# Shield_Semaforo.net
KiCad netlist of a schematic drawn in EAGLE
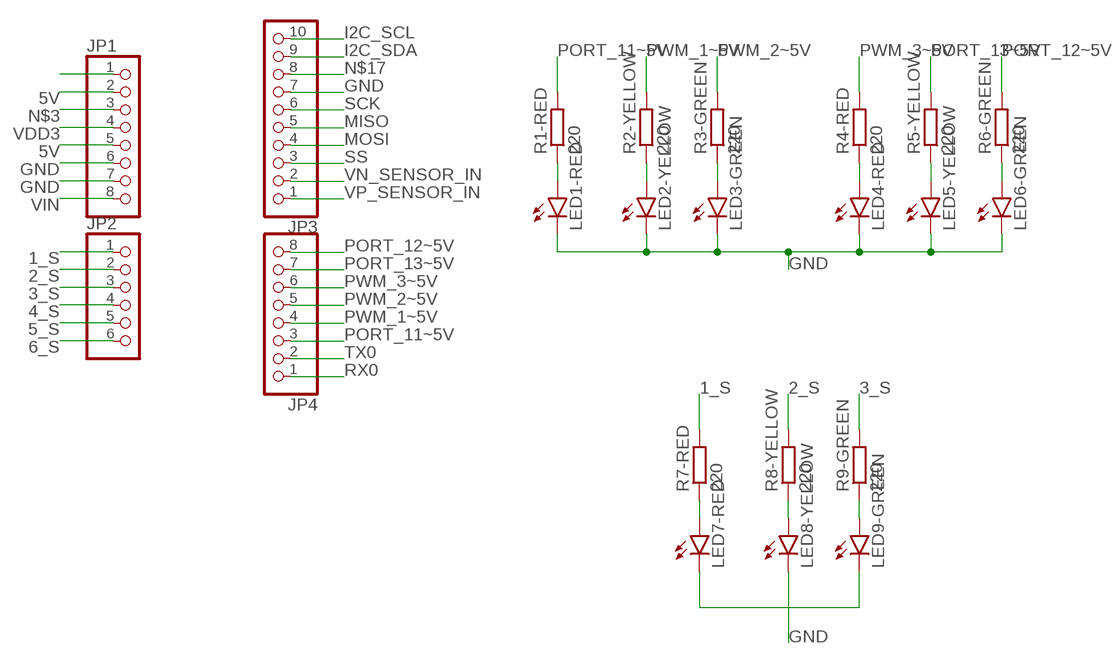
[diagram p0: schematic, sheet 1]

(export (version "E")
  (design (tool "Eeschema 10.0.6"))
  (components
    (comp (ref "JP1")
      (value "PINHD-1X8_2.54-SMD")
      (footprint "eagle-import:1X08SMD")
      (libsource (lib "eagle-import") (part "PINHD-1X8_2.54-SMD"))
    )
    (comp (ref "JP2")
      (value "PINHD-1X6_2.54-SMD")
      (footprint "eagle-import:1X06SMD")
      (libsource (lib "eagle-import") (part "PINHD-1X6_2.54-SMD"))
    )
    (comp (ref "JP3")
      (value "PINHD-1X10_2.54-SMD")
      (footprint "eagle-import:1X10SMD")
      (libsource (lib "eagle-import") (part "PINHD-1X10_2.54-SMD"))
    )
    (comp (ref "JP4")
      (value "PINHD-1X8_2.54-SMD")
      (footprint "eagle-import:1X08SMD")
      (libsource (lib "eagle-import") (part "PINHD-1X8_2.54-SMD"))
    )
    (comp (ref "LED1-RED")
      (value "LED5MM")
      (footprint "eagle-import:LED5MM")
      (libsource (lib "eagle-import") (part "LED5MM"))
    )
    (comp (ref "LED2-YELLOW")
      (value "LED5MM")
      (footprint "eagle-import:LED5MM")
      (libsource (lib "eagle-import") (part "LED5MM"))
    )
    (comp (ref "LED3-GREEN")
      (value "LED5MM")
      (footprint "eagle-import:LED5MM")
      (libsource (lib "eagle-import") (part "LED5MM"))
    )
    (comp (ref "LED4-RED")
      (value "LED5MM")
      (footprint "eagle-import:LED5MM")
      (libsource (lib "eagle-import") (part "LED5MM"))
    )
    (comp (ref "LED5-YELLOW")
      (value "LED5MM")
      (footprint "eagle-import:LED5MM")
      (libsource (lib "eagle-import") (part "LED5MM"))
    )
    (comp (ref "LED6-GREEN")
      (value "LED5MM")
      (footprint "eagle-import:LED5MM")
      (libsource (lib "eagle-import") (part "LED5MM"))
    )
    (comp (ref "LED7-RED")
      (value "LED5MM")
      (footprint "eagle-import:LED5MM")
      (libsource (lib "eagle-import") (part "LED5MM"))
    )
    (comp (ref "LED8-YELLOW")
      (value "LED5MM")
      (footprint "eagle-import:LED5MM")
      (libsource (lib "eagle-import") (part "LED5MM"))
    )
    (comp (ref "LED9-GREEN")
      (value "LED5MM")
      (footprint "eagle-import:LED5MM")
      (libsource (lib "eagle-import") (part "LED5MM"))
    )
    (comp (ref "R1-RED")
      (value "220")
      (footprint "eagle-import:M0805")
      (libsource (lib "eagle-import") (part "R-EU_M0805"))
    )
    (comp (ref "R2-YELLOW")
      (value "220")
      (footprint "eagle-import:M0805")
      (libsource (lib "eagle-import") (part "R-EU_M0805"))
    )
    (comp (ref "R3-GREEN")
      (value "220")
      (footprint "eagle-import:M0805")
      (libsource (lib "eagle-import") (part "R-EU_M0805"))
    )
    (comp (ref "R4-RED")
      (value "220")
      (footprint "eagle-import:M0805")
      (libsource (lib "eagle-import") (part "R-EU_M0805"))
    )
    (comp (ref "R5-YELLOW")
      (value "220")
      (footprint "eagle-import:M0805")
      (libsource (lib "eagle-import") (part "R-EU_M0805"))
    )
    (comp (ref "R6-GREEN")
      (value "220")
      (footprint "eagle-import:M0805")
      (libsource (lib "eagle-import") (part "R-EU_M0805"))
    )
    (comp (ref "R7-RED")
      (value "220")
      (footprint "eagle-import:M0805")
      (libsource (lib "eagle-import") (part "R-EU_M0805"))
    )
    (comp (ref "R8-YELLOW")
      (value "220")
      (footprint "eagle-import:M0805")
      (libsource (lib "eagle-import") (part "R-EU_M0805"))
    )
    (comp (ref "R9-GREEN")
      (value "220")
      (footprint "eagle-import:M0805")
      (libsource (lib "eagle-import") (part "R-EU_M0805"))
    )
  )
  (nets
    (net (code "1") (name "/1_S") (class "Default")
      (node (ref "JP2") (pin "1") (pinfunction "1_1") (pintype "passive"))
      (node (ref "R7-RED") (pin "2") (pinfunction "2_2") (pintype "passive"))
    )
    (net (code "2") (name "/2_S") (class "Default")
      (node (ref "JP2") (pin "2") (pinfunction "2_2") (pintype "passive"))
      (node (ref "R8-YELLOW") (pin "2") (pinfunction "2_2") (pintype "passive"))
    )
    (net (code "3") (name "/3_S") (class "Default")
      (node (ref "JP2") (pin "3") (pinfunction "3_3") (pintype "passive"))
      (node (ref "R9-GREEN") (pin "2") (pinfunction "2_2") (pintype "passive"))
    )
    (net (code "4") (name "/4_S") (class "Default")
      (node (ref "JP2") (pin "4") (pinfunction "4_4") (pintype "passive"))
    )
    (net (code "5") (name "/5V") (class "Default")
      (node (ref "JP1") (pin "2") (pinfunction "2_2") (pintype "passive"))
      (node (ref "JP1") (pin "5") (pinfunction "5_5") (pintype "passive"))
    )
    (net (code "6") (name "/5_S") (class "Default")
      (node (ref "JP2") (pin "5") (pinfunction "5_5") (pintype "passive"))
    )
    (net (code "7") (name "/6_S") (class "Default")
      (node (ref "JP2") (pin "6") (pinfunction "6_6") (pintype "passive"))
    )
    (net (code "8") (name "/GND") (class "Default")
      (node (ref "JP1") (pin "6") (pinfunction "6_6") (pintype "passive"))
      (node (ref "JP1") (pin "7") (pinfunction "7_7") (pintype "passive"))
      (node (ref "JP3") (pin "7") (pinfunction "7_7") (pintype "passive"))
      (node (ref "LED1-RED") (pin "K") (pinfunction "C_K") (pintype "passive"))
      (node (ref "LED2-YELLOW") (pin "K") (pinfunction "C_K") (pintype "passive"))
      (node (ref "LED3-GREEN") (pin "K") (pinfunction "C_K") (pintype "passive"))
      (node (ref "LED4-RED") (pin "K") (pinfunction "C_K") (pintype "passive"))
      (node (ref "LED5-YELLOW") (pin "K") (pinfunction "C_K") (pintype "passive"))
      (node (ref "LED6-GREEN") (pin "K") (pinfunction "C_K") (pintype "passive"))
      (node (ref "LED8-YELLOW") (pin "K") (pinfunction "C_K") (pintype "passive"))
    )
    (net (code "9") (name "/I2C_SCL") (class "Default")
      (node (ref "JP3") (pin "10") (pinfunction "10_10") (pintype "passive"))
    )
    (net (code "10") (name "/I2C_SDA") (class "Default")
      (node (ref "JP3") (pin "9") (pinfunction "9_9") (pintype "passive"))
    )
    (net (code "11") (name "/MISO") (class "Default")
      (node (ref "JP3") (pin "5") (pinfunction "5_5") (pintype "passive"))
    )
    (net (code "12") (name "/MOSI") (class "Default")
      (node (ref "JP3") (pin "4") (pinfunction "4_4") (pintype "passive"))
    )
    (net (code "13") (name "/N$3") (class "Default")
      (node (ref "JP1") (pin "3") (pinfunction "3_3") (pintype "passive"))
    )
    (net (code "14") (name "/N$17") (class "Default")
      (node (ref "JP3") (pin "8") (pinfunction "8_8") (pintype "passive"))
    )
    (net (code "15") (name "/PORT_11~{5V}") (class "Default")
      (node (ref "JP4") (pin "3") (pinfunction "3_3") (pintype "passive"))
      (node (ref "R1-RED") (pin "2") (pinfunction "2_2") (pintype "passive"))
    )
    (net (code "16") (name "/PORT_12~{5V}") (class "Default")
      (node (ref "JP4") (pin "8") (pinfunction "8_8") (pintype "passive"))
      (node (ref "R6-GREEN") (pin "2") (pinfunction "2_2") (pintype "passive"))
    )
    (net (code "17") (name "/PORT_13~{5V}") (class "Default")
      (node (ref "JP4") (pin "7") (pinfunction "7_7") (pintype "passive"))
      (node (ref "R5-YELLOW") (pin "2") (pinfunction "2_2") (pintype "passive"))
    )
    (net (code "18") (name "/PWM_1~{5V}") (class "Default")
      (node (ref "JP4") (pin "4") (pinfunction "4_4") (pintype "passive"))
      (node (ref "R2-YELLOW") (pin "2") (pinfunction "2_2") (pintype "passive"))
    )
    (net (code "19") (name "/PWM_2~{5V}") (class "Default")
      (node (ref "JP4") (pin "5") (pinfunction "5_5") (pintype "passive"))
      (node (ref "R3-GREEN") (pin "2") (pinfunction "2_2") (pintype "passive"))
    )
    (net (code "20") (name "/PWM_3~{5V}") (class "Default")
      (node (ref "JP4") (pin "6") (pinfunction "6_6") (pintype "passive"))
      (node (ref "R4-RED") (pin "2") (pinfunction "2_2") (pintype "passive"))
    )
    (net (code "21") (name "/RX0") (class "Default")
      (node (ref "JP4") (pin "1") (pinfunction "1_1") (pintype "passive"))
    )
    (net (code "22") (name "/SCK") (class "Default")
      (node (ref "JP3") (pin "6") (pinfunction "6_6") (pintype "passive"))
    )
    (net (code "23") (name "/SS") (class "Default")
      (node (ref "JP3") (pin "3") (pinfunction "3_3") (pintype "passive"))
    )
    (net (code "24") (name "/TX0") (class "Default")
      (node (ref "JP4") (pin "2") (pinfunction "2_2") (pintype "passive"))
    )
    (net (code "25") (name "/VDD3") (class "Default")
      (node (ref "JP1") (pin "4") (pinfunction "4_4") (pintype "passive"))
    )
    (net (code "26") (name "/VIN") (class "Default")
      (node (ref "JP1") (pin "8") (pinfunction "8_8") (pintype "passive"))
    )
    (net (code "27") (name "/VN_SENSOR_IN") (class "Default")
      (node (ref "JP3") (pin "2") (pinfunction "2_2") (pintype "passive"))
    )
    (net (code "28") (name "/VP_SENSOR_IN") (class "Default")
      (node (ref "JP3") (pin "1") (pinfunction "1_1") (pintype "passive"))
    )
    (net (code "29") (name "Net-(LED1-RED-PadA)") (class "Default")
      (node (ref "LED1-RED") (pin "A") (pinfunction "A_A") (pintype "passive"))
      (node (ref "R1-RED") (pin "1") (pinfunction "1_1") (pintype "passive"))
    )
    (net (code "30") (name "Net-(LED2-YELLOW-PadA)") (class "Default")
      (node (ref "LED2-YELLOW") (pin "A") (pinfunction "A_A") (pintype "passive"))
      (node (ref "R2-YELLOW") (pin "1") (pinfunction "1_1") (pintype "passive"))
    )
    (net (code "31") (name "Net-(LED3-GREEN-PadA)") (class "Default")
      (node (ref "LED3-GREEN") (pin "A") (pinfunction "A_A") (pintype "passive"))
      (node (ref "R3-GREEN") (pin "1") (pinfunction "1_1") (pintype "passive"))
    )
    (net (code "32") (name "Net-(LED4-RED-PadA)") (class "Default")
      (node (ref "LED4-RED") (pin "A") (pinfunction "A_A") (pintype "passive"))
      (node (ref "R4-RED") (pin "1") (pinfunction "1_1") (pintype "passive"))
    )
    (net (code "33") (name "Net-(LED5-YELLOW-PadA)") (class "Default")
      (node (ref "LED5-YELLOW") (pin "A") (pinfunction "A_A") (pintype "passive"))
      (node (ref "R5-YELLOW") (pin "1") (pinfunction "1_1") (pintype "passive"))
    )
    (net (code "34") (name "Net-(LED6-GREEN-PadA)") (class "Default")
      (node (ref "LED6-GREEN") (pin "A") (pinfunction "A_A") (pintype "passive"))
      (node (ref "R6-GREEN") (pin "1") (pinfunction "1_1") (pintype "passive"))
    )
    (net (code "35") (name "Net-(LED7-RED-C)") (class "Default")
      (node (ref "LED7-RED") (pin "K") (pinfunction "C_K") (pintype "passive"))
      (node (ref "LED9-GREEN") (pin "K") (pinfunction "C_K") (pintype "passive"))
    )
    (net (code "36") (name "Net-(LED7-RED-PadA)") (class "Default")
      (node (ref "LED7-RED") (pin "A") (pinfunction "A_A") (pintype "passive"))
      (node (ref "R7-RED") (pin "1") (pinfunction "1_1") (pintype "passive"))
    )
    (net (code "37") (name "Net-(LED8-YELLOW-PadA)") (class "Default")
      (node (ref "LED8-YELLOW") (pin "A") (pinfunction "A_A") (pintype "passive"))
      (node (ref "R8-YELLOW") (pin "1") (pinfunction "1_1") (pintype "passive"))
    )
    (net (code "38") (name "Net-(LED9-GREEN-PadA)") (class "Default")
      (node (ref "LED9-GREEN") (pin "A") (pinfunction "A_A") (pintype "passive"))
      (node (ref "R9-GREEN") (pin "1") (pinfunction "1_1") (pintype "passive"))
    )
    (net (code "39") (name "unconnected-(JP1-Pad1)") (class "Default")
      (node (ref "JP1") (pin "1") (pinfunction "1_1") (pintype "passive"))
    )
  )
)
